# HW_SCH.net
KiCad netlist of a schematic drawn in EasyEDA
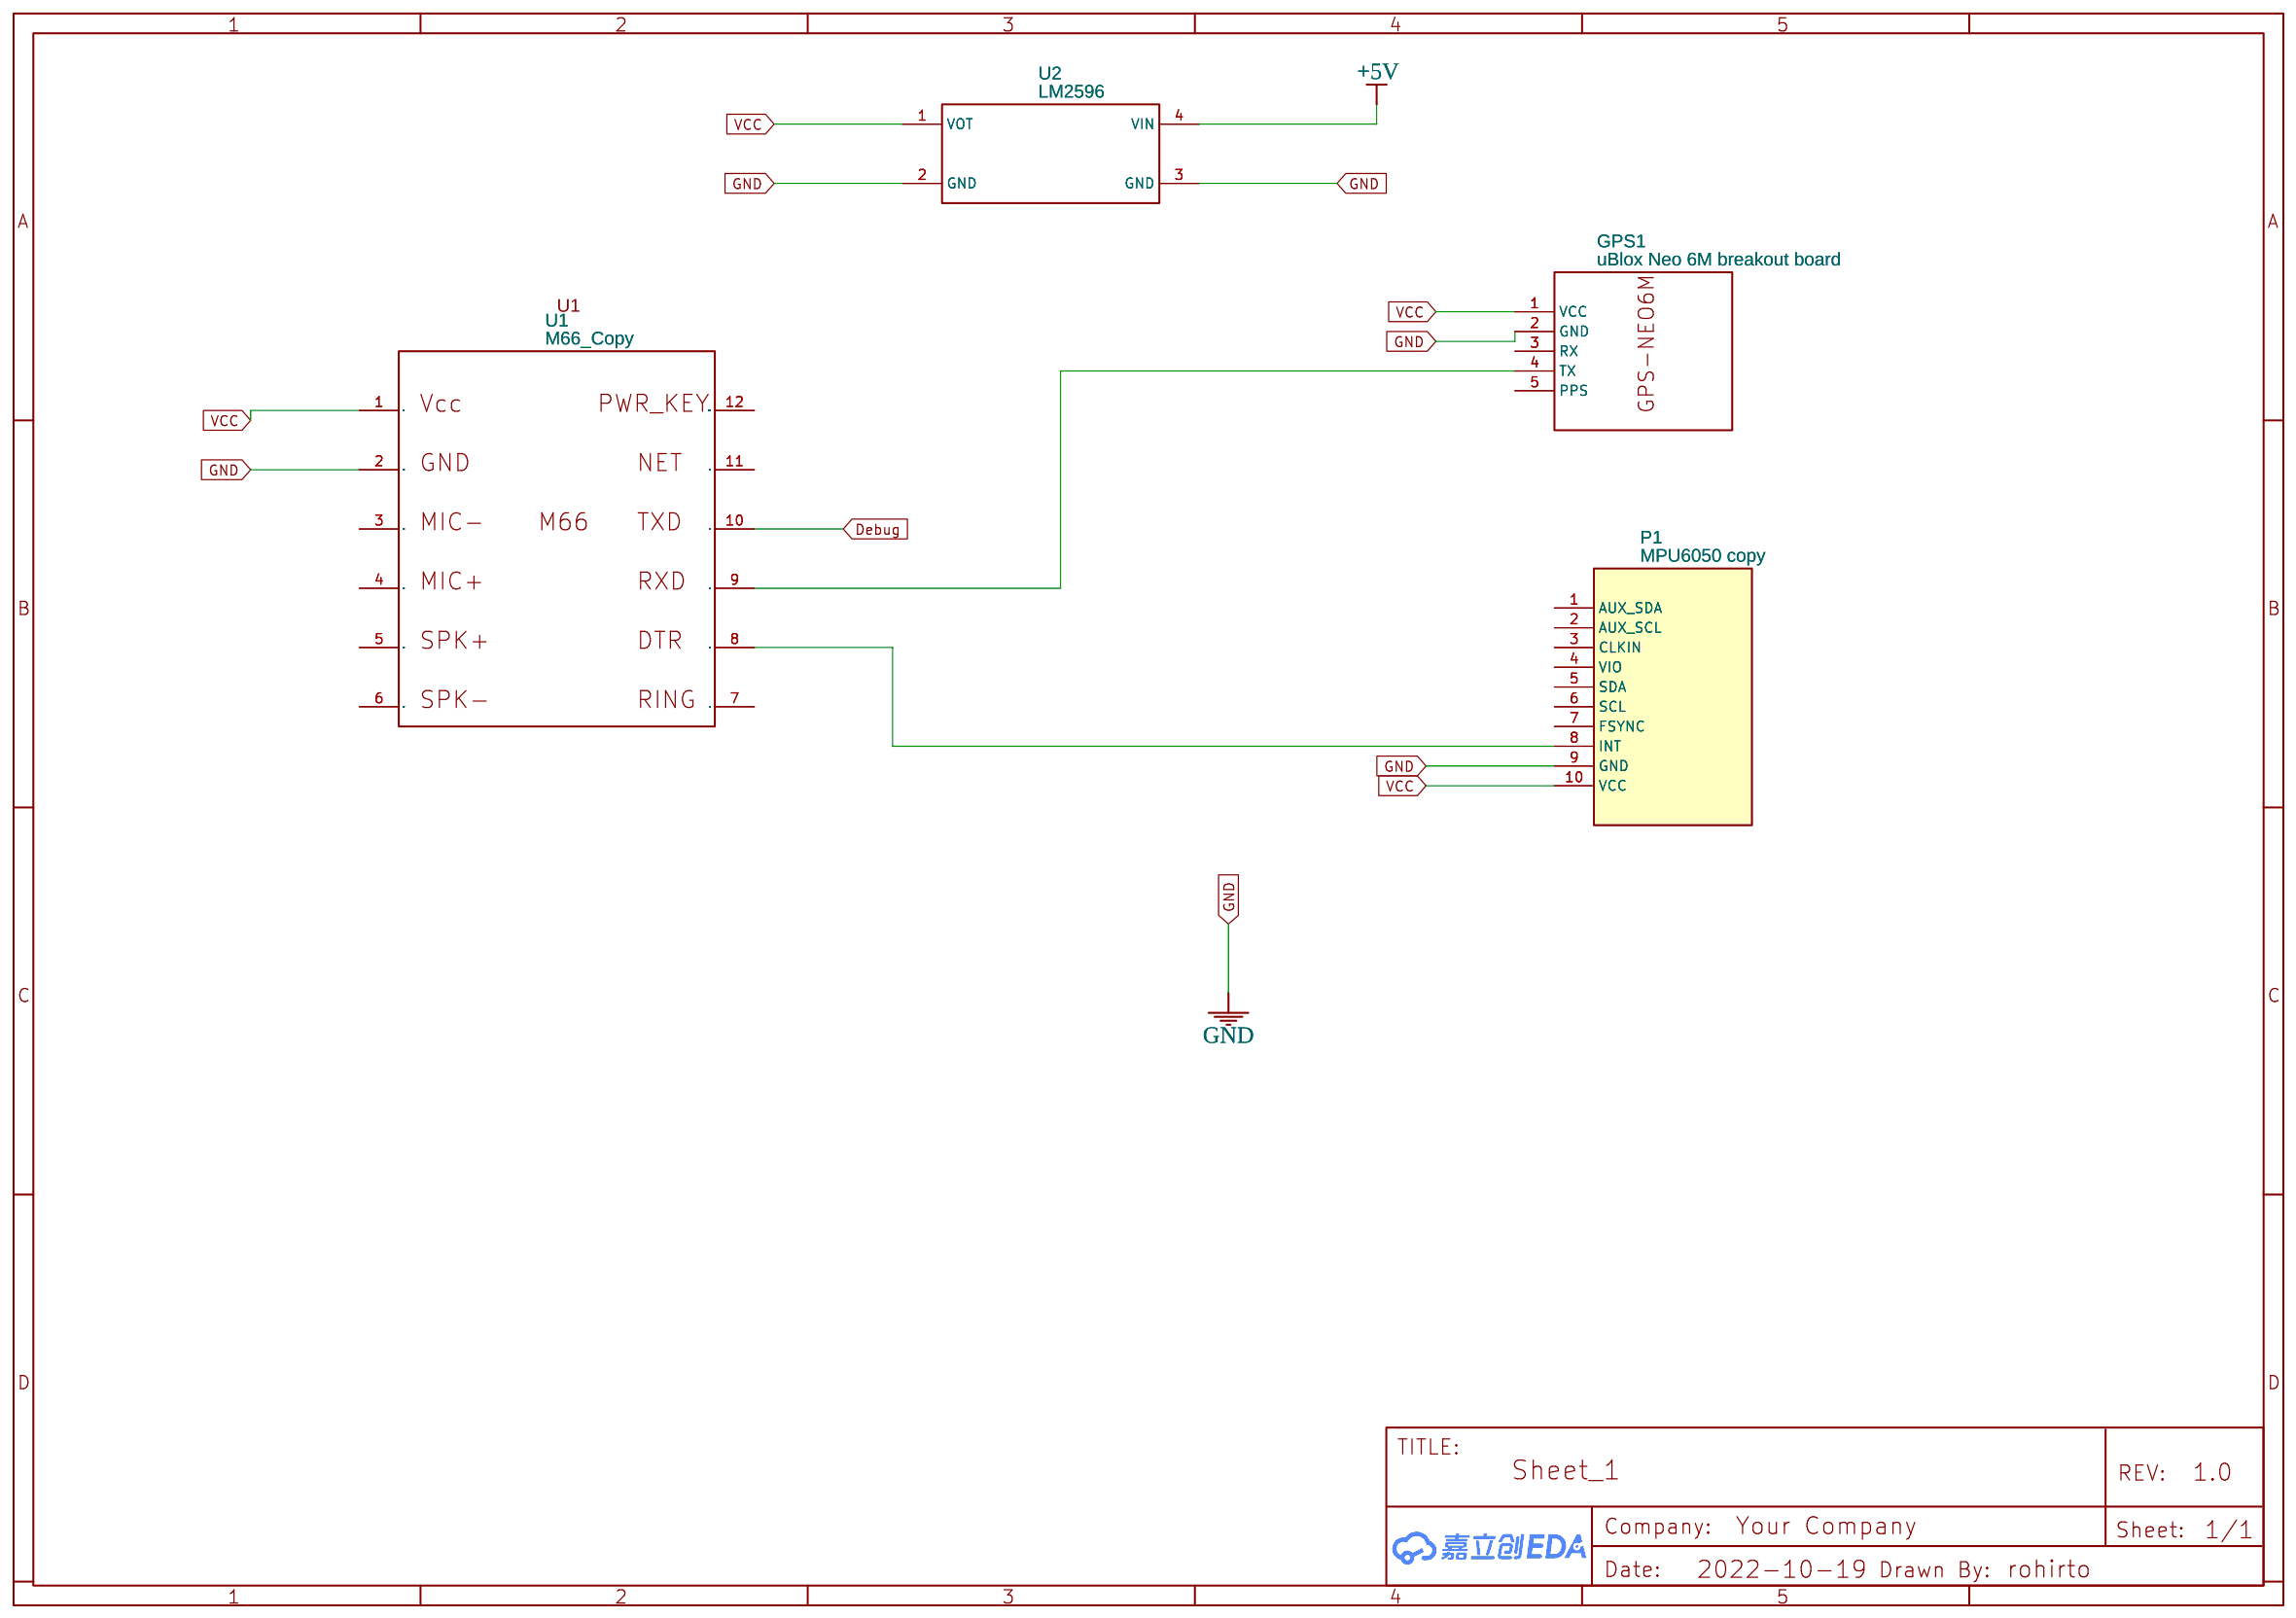
[diagram p0: schematic sheet]

(export (version "E")
  (design (tool "Eeschema 10.0.6"))
  (components
    (comp (ref "GPS1")
      (value "uBlox Neo 6M breakout board")
      (fields
        (field (name "BOM_Manufacturer Part") "GY-NEO6M")
        (field (name "BOM_Supplier Part") "GY-NEO6MV2")
      )
      (libsource (lib "") (part "uBlox Neo 6M breakout board"))
    )
    (comp (ref "P1") (value "MPU6050 copy") (libsource (lib "") (part "MPU6050 copy")))
    (comp (ref "U1")
      (value "M66_Copy")
      (fields (field (name "BOM_Manufacturer Part") "M66") (field (name "BOM_Supplier Part") "004-CM-10112"))
      (libsource (lib "") (part "M66_Copy"))
    )
    (comp (ref "U2") (value "LM2596") (libsource (lib "") (part "LM2596")))
  )
  (nets
    (net (code "1") (name "+5V") (class "Default")
      (node (ref "U2") (pin "4") (pinfunction "VIN_4") (pintype "unspecified"))
    )
    (net (code "2") (name "Debug") (class "Default")
      (node (ref "U1") (pin "10") (pinfunction "TXD_10") (pintype "output"))
    )
    (net (code "3") (name "GND") (class "Default")
      (node (ref "GPS1") (pin "2") (pinfunction "GND_2") (pintype "unspecified"))
      (node (ref "P1") (pin "9") (pinfunction "GND_9") (pintype "unspecified"))
      (node (ref "U1") (pin "2") (pinfunction "GND_2") (pintype "passive"))
      (node (ref "U2") (pin "2") (pinfunction "GND_2") (pintype "unspecified"))
      (node (ref "U2") (pin "3") (pinfunction "GND_3") (pintype "unspecified"))
    )
    (net (code "4") (name "Net-(GPS1-TX)") (class "Default")
      (node (ref "GPS1") (pin "4") (pinfunction "TX_4") (pintype "unspecified"))
      (node (ref "U1") (pin "9") (pinfunction "RXD_9") (pintype "input"))
    )
    (net (code "5") (name "Net-(P1-INT)") (class "Default")
      (node (ref "P1") (pin "8") (pinfunction "INT_8") (pintype "unspecified"))
      (node (ref "U1") (pin "8") (pinfunction "DTR_8") (pintype "bidirectional"))
    )
    (net (code "6") (name "VCC") (class "Default")
      (node (ref "GPS1") (pin "1") (pinfunction "VCC_1") (pintype "unspecified"))
      (node (ref "P1") (pin "10") (pinfunction "VCC_10") (pintype "unspecified"))
      (node (ref "U1") (pin "1") (pinfunction "Vcc_1") (pintype "passive"))
      (node (ref "U2") (pin "1") (pinfunction "VOT_1") (pintype "unspecified"))
    )
    (net (code "7") (name "unconnected-(GPS1-PPS-Pad5)") (class "Default")
      (node (ref "GPS1") (pin "5") (pinfunction "PPS_5") (pintype "unspecified"))
    )
    (net (code "8") (name "unconnected-(GPS1-RX-Pad3)") (class "Default")
      (node (ref "GPS1") (pin "3") (pinfunction "RX_3") (pintype "unspecified"))
    )
    (net (code "9") (name "unconnected-(P1-AUX_SCL-Pad2)") (class "Default")
      (node (ref "P1") (pin "2") (pinfunction "AUX_SCL_2") (pintype "unspecified"))
    )
    (net (code "10") (name "unconnected-(P1-AUX_SDA-Pad1)") (class "Default")
      (node (ref "P1") (pin "1") (pinfunction "AUX_SDA_1") (pintype "unspecified"))
    )
    (net (code "11") (name "unconnected-(P1-CLKIN-Pad3)") (class "Default")
      (node (ref "P1") (pin "3") (pinfunction "CLKIN_3") (pintype "unspecified"))
    )
    (net (code "12") (name "unconnected-(P1-FSYNC-Pad7)") (class "Default")
      (node (ref "P1") (pin "7") (pinfunction "FSYNC_7") (pintype "unspecified"))
    )
    (net (code "13") (name "unconnected-(P1-SCL-Pad6)") (class "Default")
      (node (ref "P1") (pin "6") (pinfunction "SCL_6") (pintype "unspecified"))
    )
    (net (code "14") (name "unconnected-(P1-SDA-Pad5)") (class "Default")
      (node (ref "P1") (pin "5") (pinfunction "SDA_5") (pintype "unspecified"))
    )
    (net (code "15") (name "unconnected-(P1-VIO-Pad4)") (class "Default")
      (node (ref "P1") (pin "4") (pinfunction "VIO_4") (pintype "unspecified"))
    )
    (net (code "16") (name "unconnected-(U1-MIC+-Pad4)") (class "Default")
      (node (ref "U1") (pin "4") (pinfunction "MIC+_4") (pintype "unspecified"))
    )
    (net (code "17") (name "unconnected-(U1-MIC_--Pad3)") (class "Default")
      (node (ref "U1") (pin "3") (pinfunction "MIC_-_3") (pintype "unspecified"))
    )
    (net (code "18") (name "unconnected-(U1-NET-Pad11)") (class "Default")
      (node (ref "U1") (pin "11") (pinfunction "NET_11") (pintype "unspecified"))
    )
    (net (code "19") (name "unconnected-(U1-PWR_KEY-Pad12)") (class "Default")
      (node (ref "U1") (pin "12") (pinfunction "PWR_KEY_12") (pintype "unspecified"))
    )
    (net (code "20") (name "unconnected-(U1-RI-Pad7)") (class "Default")
      (node (ref "U1") (pin "7") (pinfunction "RI_7") (pintype "bidirectional"))
    )
    (net (code "21") (name "unconnected-(U1-SPK+-Pad5)") (class "Default")
      (node (ref "U1") (pin "5") (pinfunction "SPK+_5") (pintype "unspecified"))
    )
    (net (code "22") (name "unconnected-(U1-SPK--Pad6)") (class "Default")
      (node (ref "U1") (pin "6") (pinfunction "SPK-_6") (pintype "unspecified"))
    )
  )
)
